# MS5803_Breakout.net
KiCad netlist of a schematic drawn in EAGLE
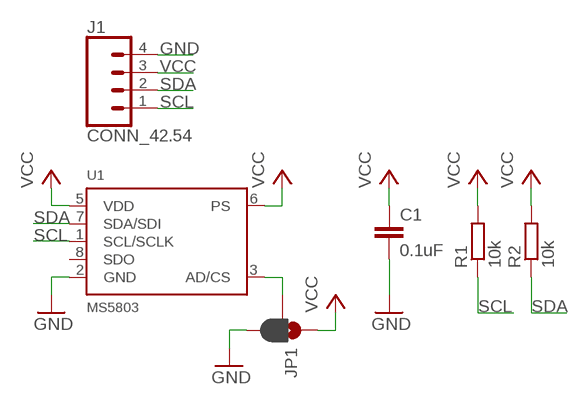
[diagram p0: schematic, sheet 1]

(export (version "E")
  (design (tool "Eeschema 10.0.6"))
  (components
    (comp (ref "C1")
      (value "0.1uF")
      (footprint "eagle-import:C0805")
      (libsource (lib "eagle-import") (part "C-EUC0805"))
    )
    (comp (ref "J1")
      (value "CONN_42.54")
      (footprint "eagle-import:1X04")
      (libsource (lib "eagle-import") (part "CONN_42.54"))
    )
    (comp (ref "JP1")
      (value "JUMPER-SMT_3_1-NC_PASTE_SILK")
      (footprint "eagle-import:SMT-JUMPER_3_1-NC_PASTE_SILK")
      (libsource (lib "eagle-import") (part "JUMPER-SMT_3_1-NC_PASTE_SILK"))
    )
    (comp (ref "R1")
      (value "10k")
      (footprint "eagle-import:R0805")
      (fields (field (name "MF") "Panasonic") (field (name "MPN") "ERA-6AEB105V"))
      (libsource (lib "eagle-import") (part "R-EU_R0805P1M"))
    )
    (comp (ref "R2")
      (value "10k")
      (footprint "eagle-import:R0805")
      (fields (field (name "MF") "Panasonic") (field (name "MPN") "ERA-6AEB105V"))
      (libsource (lib "eagle-import") (part "R-EU_R0805P1M"))
    )
    (comp (ref "U1")
      (value "MS5803")
      (footprint "eagle-import:MS5803")
      (libsource (lib "eagle-import") (part "MS5803"))
    )
  )
  (nets
    (net (code "1") (name "/SCL") (class "Default")
      (node (ref "J1") (pin "1") (pinfunction "1_1") (pintype "passive"))
      (node (ref "R1") (pin "1") (pinfunction "1_1") (pintype "passive"))
      (node (ref "U1") (pin "1") (pinfunction "SCL/SCLK_1") (pintype "bidirectional"))
    )
    (net (code "2") (name "/SDA") (class "Default")
      (node (ref "J1") (pin "2") (pinfunction "2_2") (pintype "passive"))
      (node (ref "R2") (pin "1") (pinfunction "1_1") (pintype "passive"))
      (node (ref "U1") (pin "7") (pinfunction "SDA/SDI_7") (pintype "bidirectional"))
    )
    (net (code "3") (name "GND") (class "Default")
      (node (ref "C1") (pin "2") (pinfunction "2_2") (pintype "passive"))
      (node (ref "J1") (pin "4") (pinfunction "4_4") (pintype "passive"))
      (node (ref "JP1") (pin "3") (pinfunction "3_3") (pintype "passive"))
      (node (ref "U1") (pin "2") (pinfunction "GND_2") (pintype "bidirectional"))
    )
    (net (code "4") (name "Net-(U1-AD{slash}CS)") (class "Default")
      (node (ref "JP1") (pin "2") (pinfunction "2_2") (pintype "passive"))
      (node (ref "U1") (pin "3") (pinfunction "AD/CS_3") (pintype "bidirectional"))
    )
    (net (code "5") (name "VCC") (class "Default")
      (node (ref "C1") (pin "1") (pinfunction "1_1") (pintype "passive"))
      (node (ref "J1") (pin "3") (pinfunction "3_3") (pintype "passive"))
      (node (ref "JP1") (pin "1") (pinfunction "1_1") (pintype "passive"))
      (node (ref "R1") (pin "2") (pinfunction "2_2") (pintype "passive"))
      (node (ref "R2") (pin "2") (pinfunction "2_2") (pintype "passive"))
      (node (ref "U1") (pin "5") (pinfunction "VDD_5") (pintype "bidirectional"))
      (node (ref "U1") (pin "6") (pinfunction "PS_6") (pintype "bidirectional"))
    )
    (net (code "6") (name "unconnected-(U1-SDO-Pad8)") (class "Default")
      (node (ref "U1") (pin "8") (pinfunction "SDO_8") (pintype "bidirectional"))
    )
  )
)
